# arm-pro-tiny.net
KiCad netlist of a schematic drawn in EAGLE
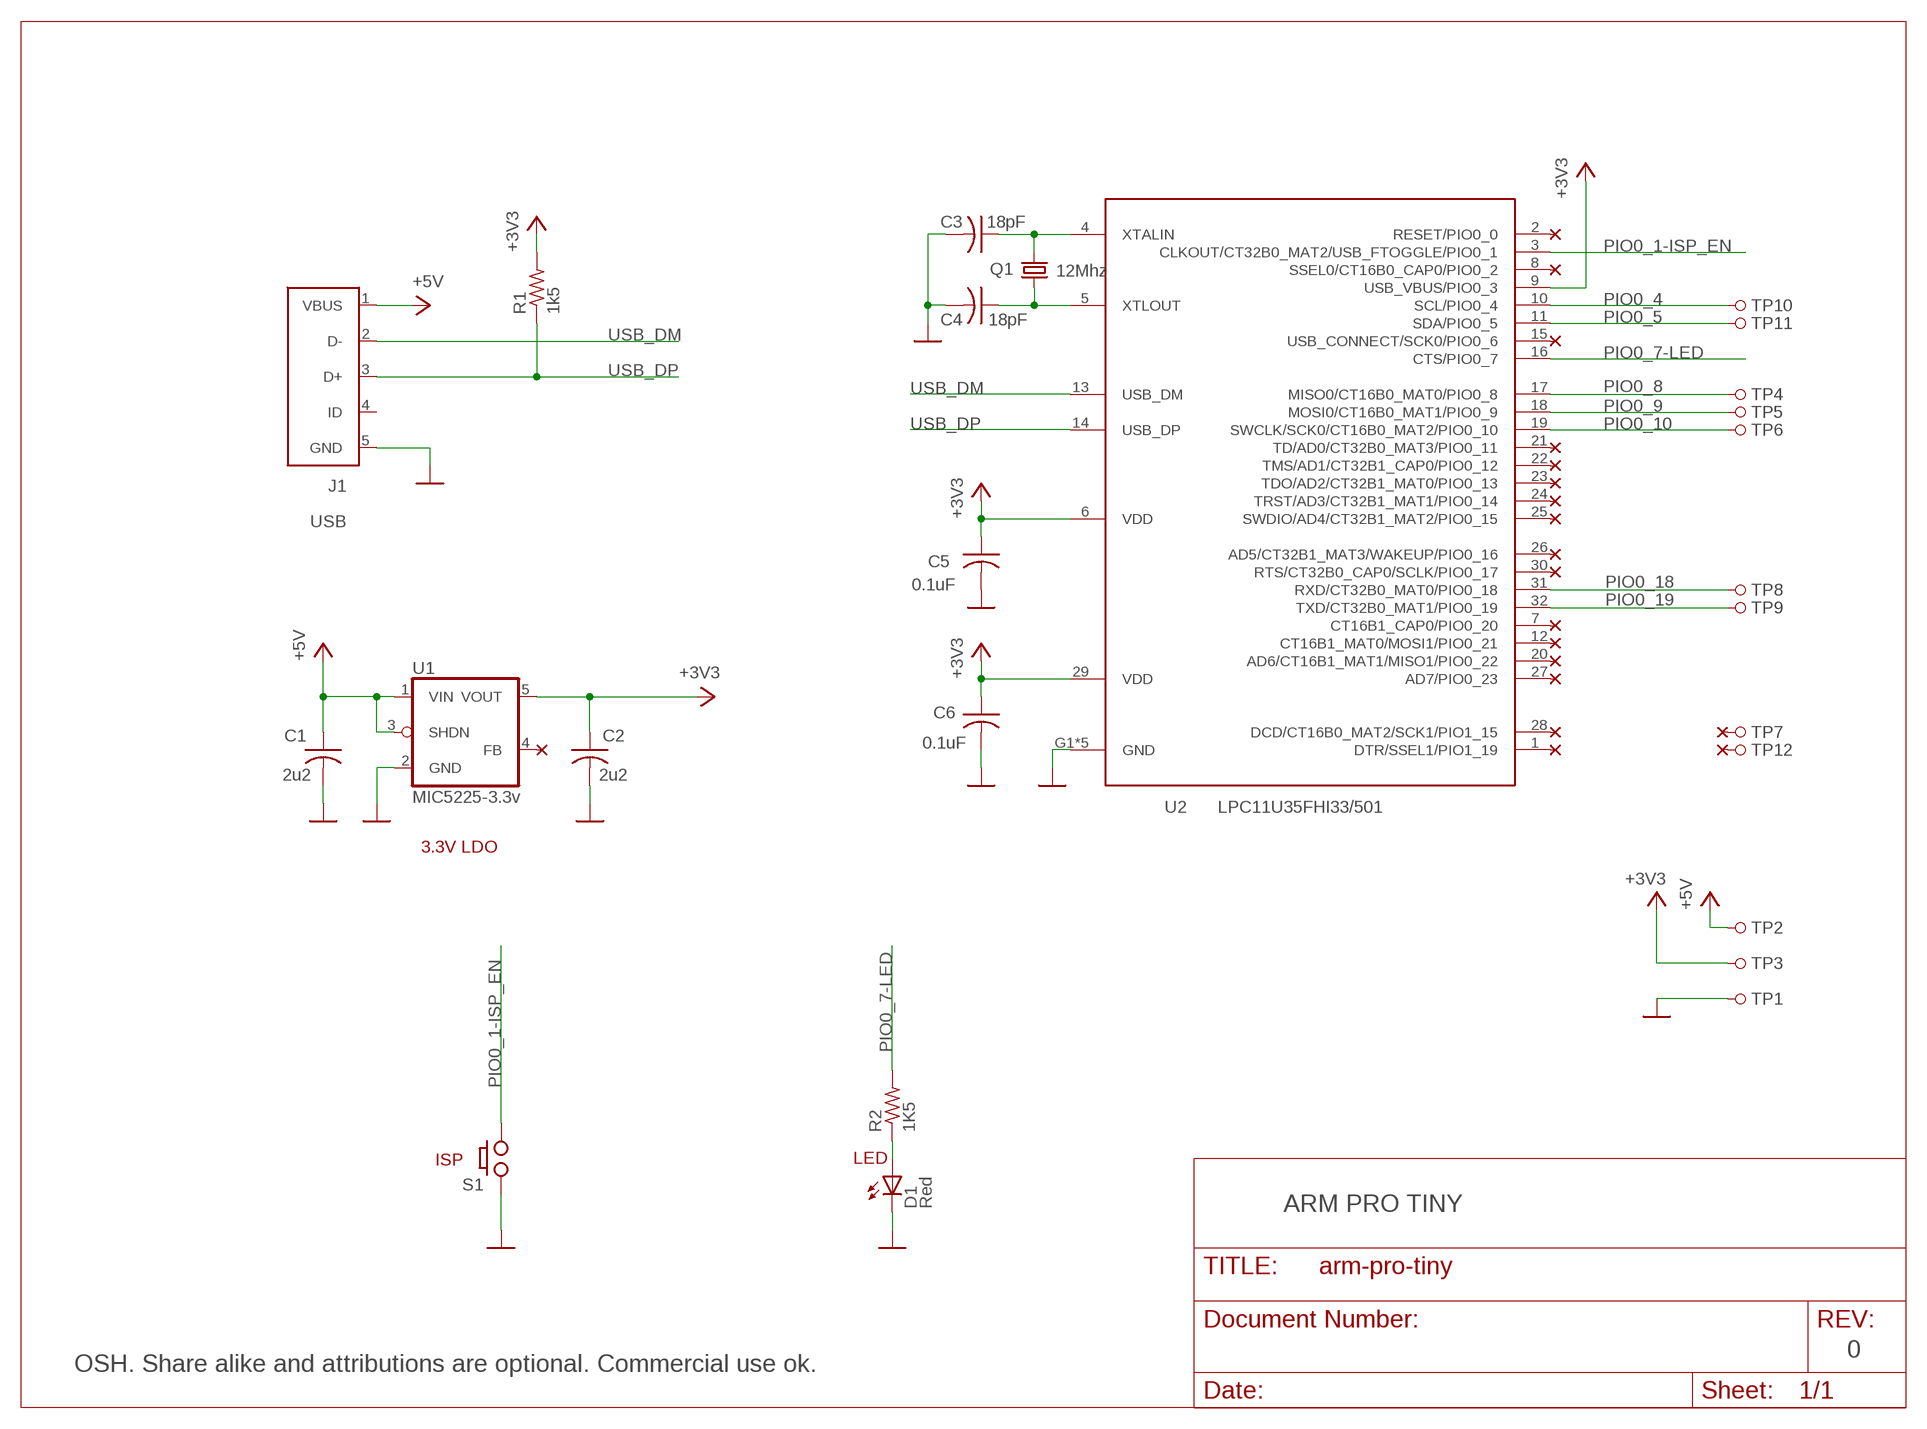
[diagram p0: schematic, sheet 1]

(export (version "E")
  (design (tool "Eeschema 10.0.6"))
  (components
    (comp (ref "C1")
      (value "2u2")
      (footprint "eagle-import:C0402K")
      (libsource (lib "eagle-import") (part "C-USC0402K"))
    )
    (comp (ref "C2")
      (value "2u2")
      (footprint "eagle-import:C0402K")
      (libsource (lib "eagle-import") (part "C-USC0402K"))
    )
    (comp (ref "C3")
      (value "18pF")
      (footprint "eagle-import:C0402K")
      (libsource (lib "eagle-import") (part "C-USC0402K"))
    )
    (comp (ref "C4")
      (value "18pF")
      (footprint "eagle-import:C0402K")
      (libsource (lib "eagle-import") (part "C-USC0402K"))
    )
    (comp (ref "C5")
      (value "0.1uF")
      (footprint "eagle-import:C0402K")
      (libsource (lib "eagle-import") (part "C-USC0402K"))
    )
    (comp (ref "C6")
      (value "0.1uF")
      (footprint "eagle-import:C0402K")
      (libsource (lib "eagle-import") (part "C-USC0402K"))
    )
    (comp (ref "D1")
      (value "Red")
      (footprint "eagle-import:CHIP-LED0603")
      (libsource (lib "eagle-import") (part "LEDCHIP-LED0603"))
    )
    (comp (ref "J1")
      (value "USB")
      (footprint "eagle-import:USB-MICRO-ZX62RD-AB-5P8")
      (libsource (lib "eagle-import") (part "USB"))
    )
    (comp (ref "Q1")
      (value "12Mhz")
      (footprint "eagle-import:CRYSTAL")
      (libsource (lib "eagle-import") (part "CRYSTALCTS406"))
    )
    (comp (ref "R1")
      (value "1k5")
      (footprint "eagle-import:R0402")
      (libsource (lib "eagle-import") (part "R-US_R0402"))
    )
    (comp (ref "R2")
      (value "1K5")
      (footprint "eagle-import:R0402")
      (libsource (lib "eagle-import") (part "R-US_R0402"))
    )
    (comp (ref "S1")
      (value "PUSH_BUTTON")
      (footprint "eagle-import:PUSH_BUTTON")
      (libsource (lib "eagle-import") (part "PUSH_BUTTON"))
    )
    (comp (ref "TP1")
      (value "HDR1")
      (footprint "eagle-import:1X01")
      (libsource (lib "eagle-import") (part "PINHD-1X1"))
    )
    (comp (ref "TP2")
      (value "HDR1")
      (footprint "eagle-import:1X01")
      (libsource (lib "eagle-import") (part "PINHD-1X1"))
    )
    (comp (ref "TP3")
      (value "HDR1")
      (footprint "eagle-import:1X01")
      (libsource (lib "eagle-import") (part "PINHD-1X1"))
    )
    (comp (ref "TP4")
      (value "HDR1")
      (footprint "eagle-import:1X01")
      (libsource (lib "eagle-import") (part "PINHD-1X1"))
    )
    (comp (ref "TP5")
      (value "HDR1")
      (footprint "eagle-import:1X01")
      (libsource (lib "eagle-import") (part "PINHD-1X1"))
    )
    (comp (ref "TP6")
      (value "HDR1")
      (footprint "eagle-import:1X01")
      (libsource (lib "eagle-import") (part "PINHD-1X1"))
    )
    (comp (ref "TP7")
      (value "HDR1")
      (footprint "eagle-import:1X01")
      (libsource (lib "eagle-import") (part "PINHD-1X1"))
    )
    (comp (ref "TP8")
      (value "HDR1")
      (footprint "eagle-import:1X01")
      (libsource (lib "eagle-import") (part "PINHD-1X1"))
    )
    (comp (ref "TP9")
      (value "HDR1")
      (footprint "eagle-import:1X01")
      (libsource (lib "eagle-import") (part "PINHD-1X1"))
    )
    (comp (ref "TP10")
      (value "HDR1")
      (footprint "eagle-import:1X01")
      (libsource (lib "eagle-import") (part "PINHD-1X1"))
    )
    (comp (ref "TP11")
      (value "HDR1")
      (footprint "eagle-import:1X01")
      (libsource (lib "eagle-import") (part "PINHD-1X1"))
    )
    (comp (ref "TP12")
      (value "HDR1")
      (footprint "eagle-import:1X01")
      (libsource (lib "eagle-import") (part "PINHD-1X1"))
    )
    (comp (ref "U1")
      (value "MIC5225-3.3v")
      (footprint "eagle-import:SOT25")
      (libsource (lib "eagle-import") (part "TC1015"))
    )
    (comp (ref "U2")
      (value "LPC11U35FHI33/501")
      (footprint "eagle-import:HVQFN33-5MM")
      (libsource (lib "eagle-import") (part "LPC11U35FHN33/501"))
    )
  )
  (nets
    (net (code "1") (name "+3V3") (class "Default")
      (node (ref "C2") (pin "1") (pinfunction "1_1") (pintype "passive"))
      (node (ref "C5") (pin "1") (pinfunction "1_1") (pintype "passive"))
      (node (ref "C6") (pin "1") (pinfunction "1_1") (pintype "passive"))
      (node (ref "R1") (pin "2") (pinfunction "2_2") (pintype "passive"))
      (node (ref "TP3") (pin "1") (pinfunction "1_1") (pintype "passive"))
      (node (ref "U1") (pin "5") (pinfunction "VOUT_5") (pintype "power_in"))
      (node (ref "U2") (pin "29") (pinfunction "VDD_29") (pintype "bidirectional"))
      (node (ref "U2") (pin "6") (pinfunction "VDD_6") (pintype "bidirectional"))
      (node (ref "U2") (pin "9") (pinfunction "USB_VBUS/PIO0_3_9") (pintype "bidirectional"))
    )
    (net (code "2") (name "+5V") (class "Default")
      (node (ref "C1") (pin "1") (pinfunction "1_1") (pintype "passive"))
      (node (ref "J1") (pin "1") (pinfunction "VBUS_1") (pintype "bidirectional"))
      (node (ref "TP2") (pin "1") (pinfunction "1_1") (pintype "passive"))
      (node (ref "U1") (pin "1") (pinfunction "VIN_1") (pintype "power_in"))
      (node (ref "U1") (pin "3") (pinfunction "SHDN_3") (pintype "input"))
    )
    (net (code "3") (name "/PIO0_1-ISP_EN") (class "Default")
      (node (ref "S1") (pin "B2") (pinfunction "2_B2") (pintype "passive"))
      (node (ref "U2") (pin "3") (pinfunction "CLKOUT/CT32B0_MAT2/USB_FTOGGLE/PIO0_1_3") (pintype "bidirectional"))
    )
    (net (code "4") (name "/PIO0_4") (class "Default")
      (node (ref "TP10") (pin "1") (pinfunction "1_1") (pintype "passive"))
      (node (ref "U2") (pin "10") (pinfunction "SCL/PIO0_4_10") (pintype "bidirectional"))
    )
    (net (code "5") (name "/PIO0_5") (class "Default")
      (node (ref "TP11") (pin "1") (pinfunction "1_1") (pintype "passive"))
      (node (ref "U2") (pin "11") (pinfunction "SDA/PIO0_5_11") (pintype "bidirectional"))
    )
    (net (code "6") (name "/PIO0_7-LED") (class "Default")
      (node (ref "R2") (pin "2") (pinfunction "2_2") (pintype "passive"))
      (node (ref "U2") (pin "16") (pinfunction "CTS/PIO0_7_16") (pintype "bidirectional"))
    )
    (net (code "7") (name "/PIO0_8") (class "Default")
      (node (ref "TP4") (pin "1") (pinfunction "1_1") (pintype "passive"))
      (node (ref "U2") (pin "17") (pinfunction "MISO0/CT16B0_MAT0/PIO0_8_17") (pintype "bidirectional"))
    )
    (net (code "8") (name "/PIO0_9") (class "Default")
      (node (ref "TP5") (pin "1") (pinfunction "1_1") (pintype "passive"))
      (node (ref "U2") (pin "18") (pinfunction "MOSI0/CT16B0_MAT1/PIO0_9_18") (pintype "bidirectional"))
    )
    (net (code "9") (name "/PIO0_10") (class "Default")
      (node (ref "TP6") (pin "1") (pinfunction "1_1") (pintype "passive"))
      (node (ref "U2") (pin "19") (pinfunction "SWCLK/SCK0/CT16B0_MAT2/PIO0_10_19") (pintype "bidirectional"))
    )
    (net (code "10") (name "/PIO0_18") (class "Default")
      (node (ref "TP8") (pin "1") (pinfunction "1_1") (pintype "passive"))
      (node (ref "U2") (pin "31") (pinfunction "RXD/CT32B0_MAT0/PIO0_18_31") (pintype "bidirectional"))
    )
    (net (code "11") (name "/PIO0_19") (class "Default")
      (node (ref "TP9") (pin "1") (pinfunction "1_1") (pintype "passive"))
      (node (ref "U2") (pin "32") (pinfunction "TXD/CT32B0_MAT1/PIO0_19_32") (pintype "bidirectional"))
    )
    (net (code "12") (name "/USB_DM") (class "Default")
      (node (ref "J1") (pin "2") (pinfunction "D-_2") (pintype "bidirectional"))
      (node (ref "U2") (pin "13") (pinfunction "USB_DM_13") (pintype "bidirectional"))
    )
    (net (code "13") (name "/USB_DP") (class "Default")
      (node (ref "J1") (pin "3") (pinfunction "D+_3") (pintype "bidirectional"))
      (node (ref "R1") (pin "1") (pinfunction "1_1") (pintype "passive"))
      (node (ref "U2") (pin "14") (pinfunction "USB_DP_14") (pintype "bidirectional"))
    )
    (net (code "14") (name "GND") (class "Default")
      (node (ref "C1") (pin "2") (pinfunction "2_2") (pintype "passive"))
      (node (ref "C2") (pin "2") (pinfunction "2_2") (pintype "passive"))
      (node (ref "C3") (pin "2") (pinfunction "2_2") (pintype "passive"))
      (node (ref "C4") (pin "2") (pinfunction "2_2") (pintype "passive"))
      (node (ref "C5") (pin "2") (pinfunction "2_2") (pintype "passive"))
      (node (ref "C6") (pin "2") (pinfunction "2_2") (pintype "passive"))
      (node (ref "D1") (pin "C") (pinfunction "C_C") (pintype "passive"))
      (node (ref "J1") (pin "5") (pinfunction "GND_5") (pintype "bidirectional"))
      (node (ref "S1") (pin "A1") (pinfunction "1_A1") (pintype "passive"))
      (node (ref "TP1") (pin "1") (pinfunction "1_1") (pintype "passive"))
      (node (ref "U1") (pin "2") (pinfunction "GND_2") (pintype "power_in"))
      (node (ref "U2") (pin "G1") (pinfunction "GND_G1") (pintype "bidirectional"))
      (node (ref "U2") (pin "G2") (pinfunction "GND_G2") (pintype "bidirectional"))
      (node (ref "U2") (pin "G3") (pinfunction "GND_G3") (pintype "bidirectional"))
      (node (ref "U2") (pin "G4") (pinfunction "GND_G4") (pintype "bidirectional"))
      (node (ref "U2") (pin "TAB") (pinfunction "GND_TAB") (pintype "bidirectional"))
    )
    (net (code "15") (name "Net-(D1-PadA)") (class "Default")
      (node (ref "D1") (pin "A") (pinfunction "A_A") (pintype "passive"))
      (node (ref "R2") (pin "1") (pinfunction "1_1") (pintype "passive"))
    )
    (net (code "16") (name "Net-(Q1-2)") (class "Default")
      (node (ref "C3") (pin "1") (pinfunction "1_1") (pintype "passive"))
      (node (ref "Q1") (pin "3") (pinfunction "2_3") (pintype "passive"))
      (node (ref "U2") (pin "4") (pinfunction "XTALIN_4") (pintype "bidirectional"))
    )
    (net (code "17") (name "Net-(U2-XTLOUT)") (class "Default")
      (node (ref "C4") (pin "1") (pinfunction "1_1") (pintype "passive"))
      (node (ref "Q1") (pin "1") (pinfunction "1_1") (pintype "passive"))
      (node (ref "U2") (pin "5") (pinfunction "XTLOUT_5") (pintype "bidirectional"))
    )
    (net (code "18") (name "unconnected-(J1-ID-Pad4)") (class "Default")
      (node (ref "J1") (pin "4") (pinfunction "ID_4") (pintype "bidirectional"))
    )
    (net (code "19") (name "unconnected-(TP7-Pad1)") (class "Default")
      (node (ref "TP7") (pin "1") (pinfunction "1_1") (pintype "passive"))
    )
    (net (code "20") (name "unconnected-(TP12-Pad1)") (class "Default")
      (node (ref "TP12") (pin "1") (pinfunction "1_1") (pintype "passive"))
    )
    (net (code "21") (name "unconnected-(U1-FB-Pad4)") (class "Default")
      (node (ref "U1") (pin "4") (pinfunction "FB_4") (pintype "passive"))
    )
    (net (code "22") (name "unconnected-(U2-AD5{slash}CT32B1_MAT3{slash}WAKEUP{slash}PIO0_16-Pad26)") (class "Default")
      (node (ref "U2") (pin "26") (pinfunction "AD5/CT32B1_MAT3/WAKEUP/PIO0_16_26") (pintype "bidirectional"))
    )
    (net (code "23") (name "unconnected-(U2-AD6{slash}CT16B1_MAT1{slash}MISO1{slash}PIO0_22-Pad20)") (class "Default")
      (node (ref "U2") (pin "20") (pinfunction "AD6/CT16B1_MAT1/MISO1/PIO0_22_20") (pintype "bidirectional"))
    )
    (net (code "24") (name "unconnected-(U2-AD7{slash}PIO0_23-Pad27)") (class "Default")
      (node (ref "U2") (pin "27") (pinfunction "AD7/PIO0_23_27") (pintype "bidirectional"))
    )
    (net (code "25") (name "unconnected-(U2-CT16B1_CAP0{slash}PIO0_20-Pad7)") (class "Default")
      (node (ref "U2") (pin "7") (pinfunction "CT16B1_CAP0/PIO0_20_7") (pintype "bidirectional"))
    )
    (net (code "26") (name "unconnected-(U2-CT16B1_MAT0{slash}MOSI1{slash}PIO0_21-Pad12)") (class "Default")
      (node (ref "U2") (pin "12") (pinfunction "CT16B1_MAT0/MOSI1/PIO0_21_12") (pintype "bidirectional"))
    )
    (net (code "27") (name "unconnected-(U2-DCD{slash}CT16B0_MAT2{slash}SCK1{slash}PIO1_15-Pad28)") (class "Default")
      (node (ref "U2") (pin "28") (pinfunction "DCD/CT16B0_MAT2/SCK1/PIO1_15_28") (pintype "bidirectional"))
    )
    (net (code "28") (name "unconnected-(U2-DTR{slash}SSEL1{slash}PIO1_19-Pad1)") (class "Default")
      (node (ref "U2") (pin "1") (pinfunction "DTR/SSEL1/PIO1_19_1") (pintype "bidirectional"))
    )
    (net (code "29") (name "unconnected-(U2-RESET{slash}PIO0_0-Pad2)") (class "Default")
      (node (ref "U2") (pin "2") (pinfunction "RESET/PIO0_0_2") (pintype "bidirectional"))
    )
    (net (code "30") (name "unconnected-(U2-RTS{slash}CT32B0_CAP0{slash}SCLK{slash}PIO0_17-Pad30)") (class "Default")
      (node (ref "U2") (pin "30") (pinfunction "RTS/CT32B0_CAP0/SCLK/PIO0_17_30") (pintype "bidirectional"))
    )
    (net (code "31") (name "unconnected-(U2-SSEL0{slash}CT16B0_CAP0{slash}PIO0_2-Pad8)") (class "Default")
      (node (ref "U2") (pin "8") (pinfunction "SSEL0/CT16B0_CAP0/PIO0_2_8") (pintype "bidirectional"))
    )
    (net (code "32") (name "unconnected-(U2-SWDIO{slash}AD4{slash}CT32B1_MAT2{slash}PIO0_15-Pad25)") (class "Default")
      (node (ref "U2") (pin "25") (pinfunction "SWDIO/AD4/CT32B1_MAT2/PIO0_15_25") (pintype "bidirectional"))
    )
    (net (code "33") (name "unconnected-(U2-TDO{slash}AD2{slash}CT32B1_MAT0{slash}PIO0_13-Pad23)") (class "Default")
      (node (ref "U2") (pin "23") (pinfunction "TDO/AD2/CT32B1_MAT0/PIO0_13_23") (pintype "bidirectional"))
    )
    (net (code "34") (name "unconnected-(U2-TD{slash}AD0{slash}CT32B0_MAT3{slash}PIO0_11-Pad21)") (class "Default")
      (node (ref "U2") (pin "21") (pinfunction "TD/AD0/CT32B0_MAT3/PIO0_11_21") (pintype "bidirectional"))
    )
    (net (code "35") (name "unconnected-(U2-TMS{slash}AD1{slash}CT32B1_CAP0{slash}PIO0_12-Pad22)") (class "Default")
      (node (ref "U2") (pin "22") (pinfunction "TMS/AD1/CT32B1_CAP0/PIO0_12_22") (pintype "bidirectional"))
    )
    (net (code "36") (name "unconnected-(U2-TRST{slash}AD3{slash}CT32B1_MAT1{slash}PIO0_14-Pad24)") (class "Default")
      (node (ref "U2") (pin "24") (pinfunction "TRST/AD3/CT32B1_MAT1/PIO0_14_24") (pintype "bidirectional"))
    )
    (net (code "37") (name "unconnected-(U2-USB_CONNECT{slash}SCK0{slash}PIO0_6-Pad15)") (class "Default")
      (node (ref "U2") (pin "15") (pinfunction "USB_CONNECT/SCK0/PIO0_6_15") (pintype "bidirectional"))
    )
  )
)
